# Sheet_1_2022-05-04.net
KiCad netlist of a schematic drawn in Altium Designer
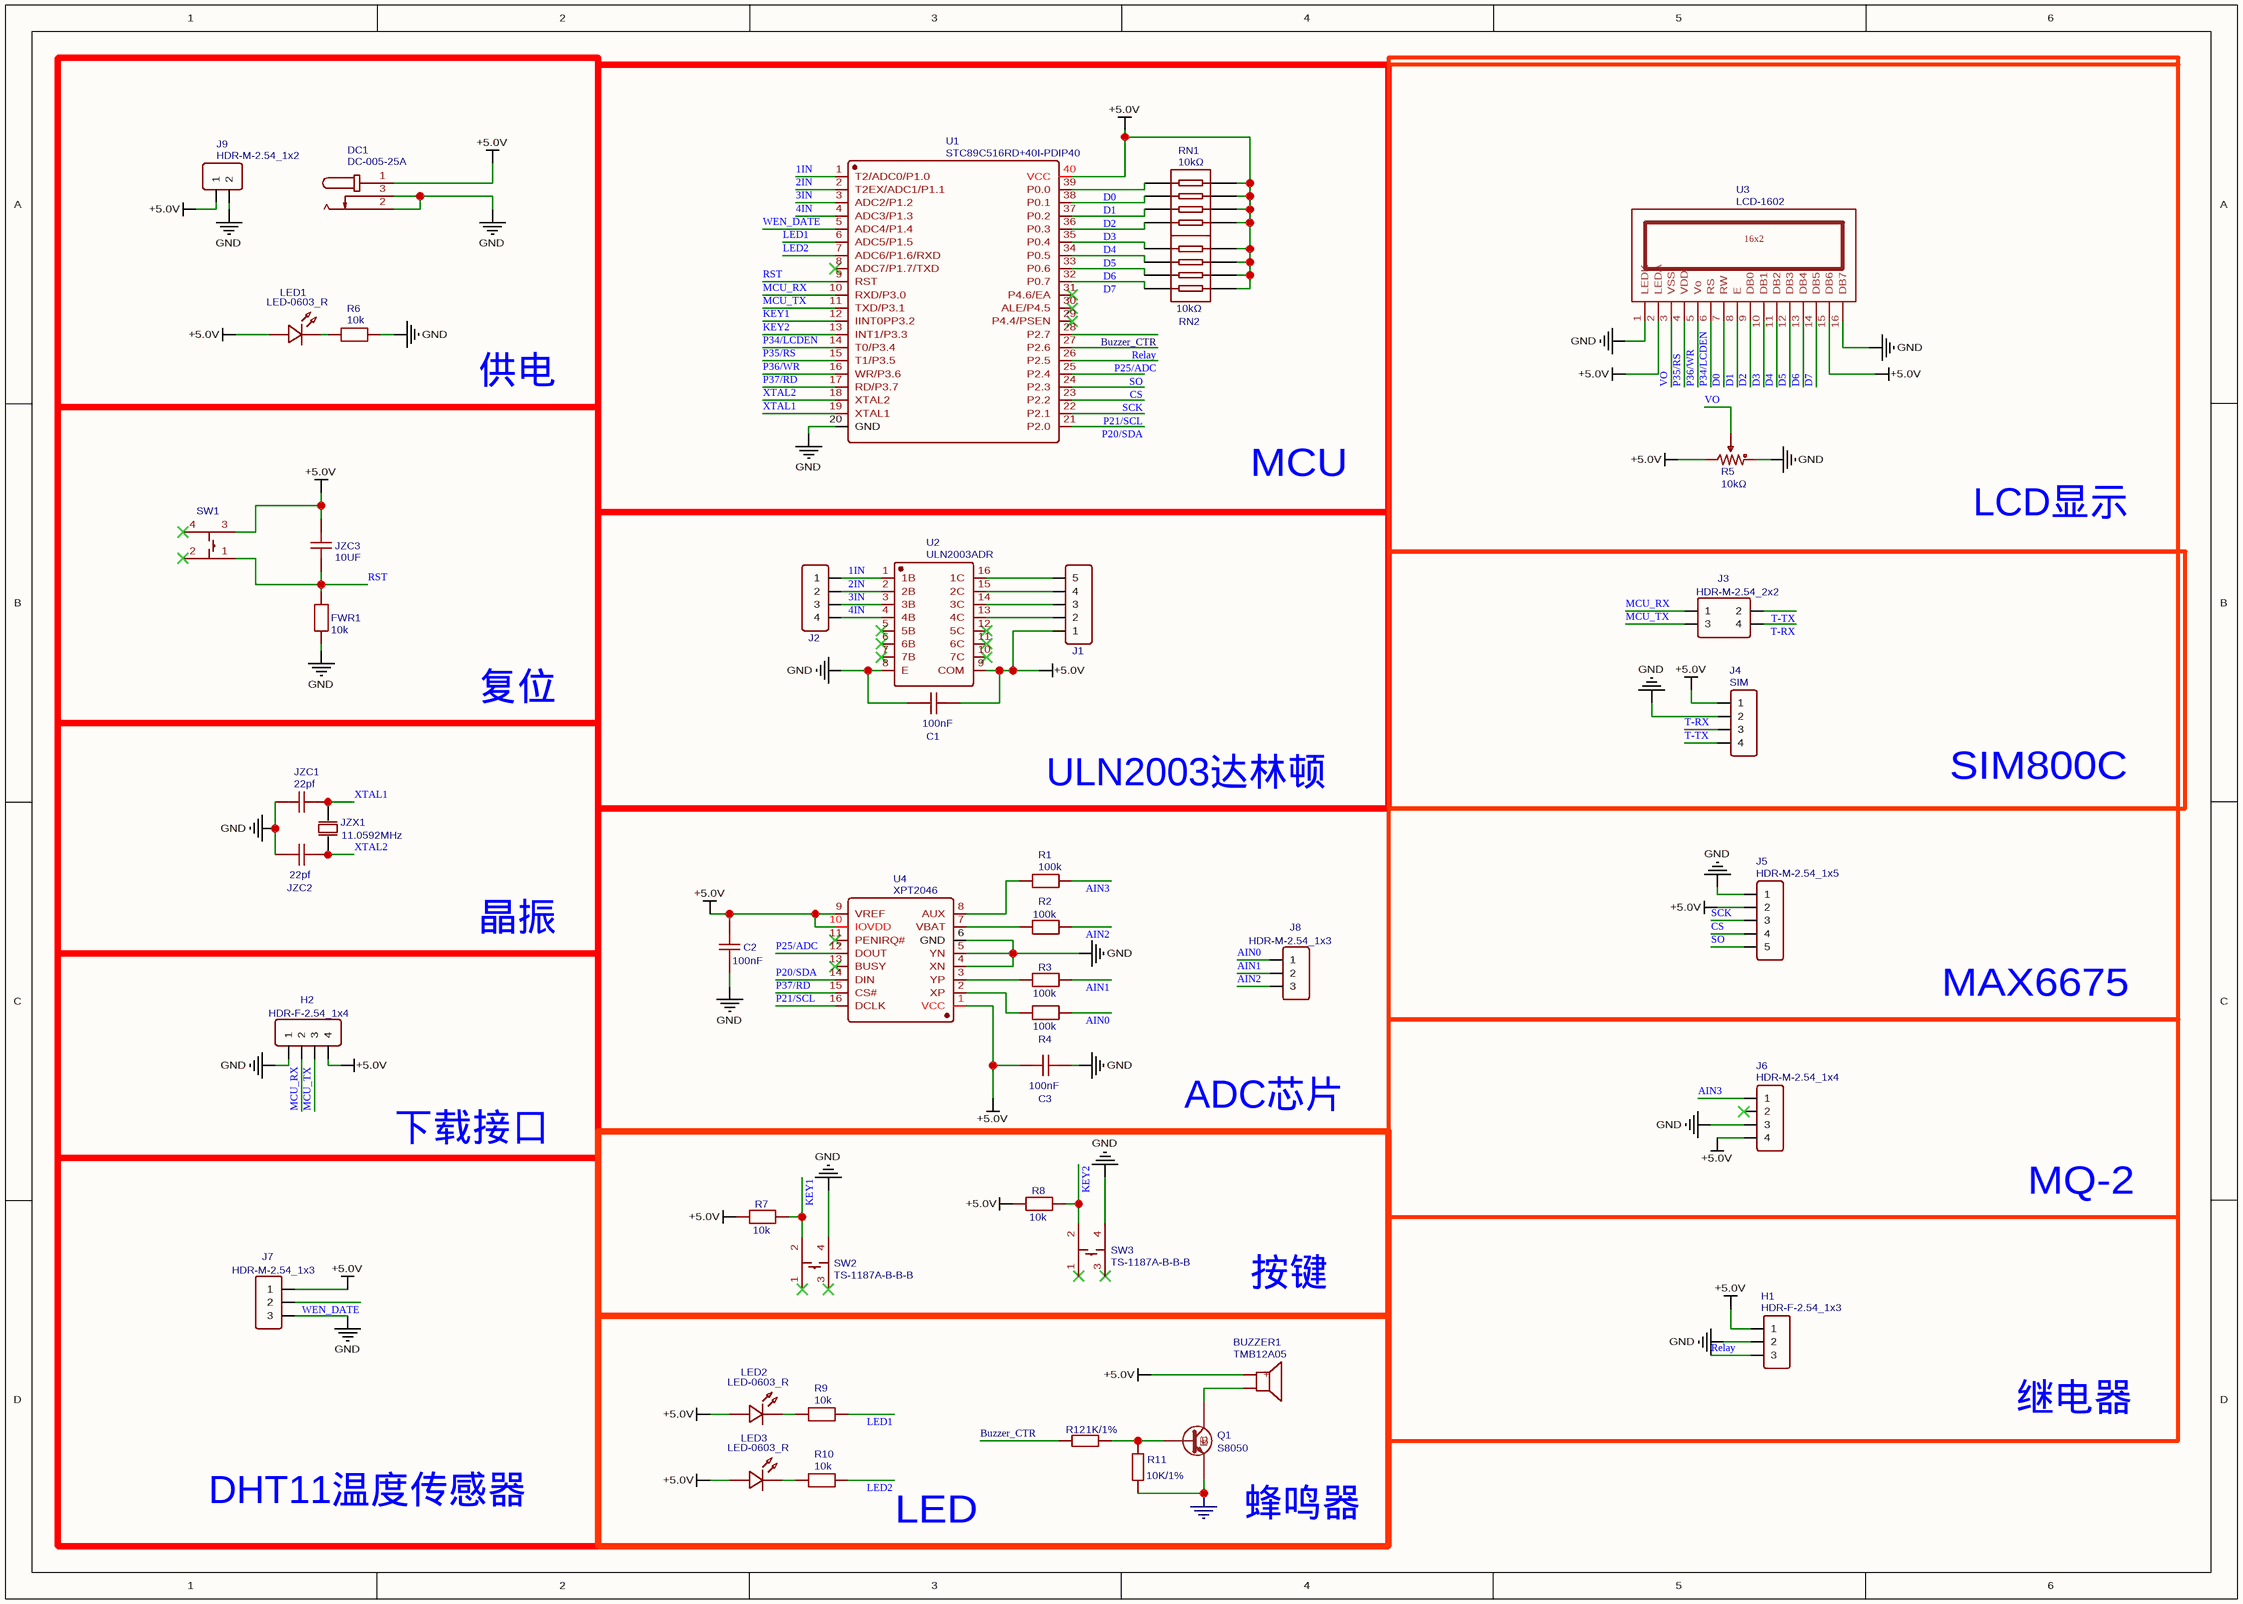
[diagram p0: Sheet_1_2022-05-04.schdoc]

(export (version "E")
  (design (tool "Eeschema 10.0.6"))
  (components
    (comp (ref "BUZZER1")
      (value "TMB12A05")
      (fields (field (name "BOM_SUPPLIER PART") "C96093"))
      (libsource (lib "altium-import") (part "root_0_TMB12A05_"))
    )
    (comp (ref "C1")
      (value "100nF")
      (fields (field (name "CONTRIBUTOR") "LCEDA_Lib"))
      (libsource (lib "altium-import") (part "root_0_100nF_"))
    )
    (comp (ref "C2")
      (value "100nF")
      (fields (field (name "CONTRIBUTOR") "LCEDA_Lib"))
      (libsource (lib "altium-import") (part "root_1_100nF_"))
    )
    (comp (ref "C3")
      (value "100nF")
      (fields (field (name "CONTRIBUTOR") "LCEDA_Lib"))
      (libsource (lib "altium-import") (part "root_0_100nF_"))
    )
    (comp (ref "DC1")
      (value "DC-005-25A")
      (fields (field (name "BOM_SUPPLIER PART") "C136715") (field (name "CONTRIBUTOR") "LCSC"))
      (libsource (lib "altium-import") (part "root_0_DC-005-25A_"))
    )
    (comp (ref "FWR1")
      (value "10k")
      (fields (field (name "CONTRIBUTOR") "LCEDA_Lib"))
      (libsource (lib "altium-import") (part "root_1_10k_"))
    )
    (comp (ref "H1")
      (value "HDR-F-2.54_1x3")
      (fields (field (name "BOM_SUPPLIER PART") "C146690") (field (name "CONTRIBUTOR") "LCEDA_Lib"))
      (libsource (lib "altium-import") (part "root_0_HDR-F-2.54_1x3_"))
    )
    (comp (ref "H2")
      (value "HDR-F-2.54_1x4")
      (fields (field (name "BOM_SUPPLIER PART") "C225501") (field (name "CONTRIBUTOR") "LCEDA_Lib"))
      (libsource (lib "altium-import") (part "root_1_HDR-F-2.54_1x4_"))
    )
    (comp (ref "J1")
      (value "HDR-M-2.54_1x5")
      (fields (field (name "BOM_SUPPLIER PART") "C358687") (field (name "CONTRIBUTOR") "LCEDA_Lib"))
      (libsource (lib "") (part "root_0_HDR-M-2.54_1x5__1"))
    )
    (comp (ref "J2")
      (value "HDR-M-2.54_1x4")
      (fields (field (name "BOM_SUPPLIER PART") "C124378") (field (name "CONTRIBUTOR") "LCEDA_Lib"))
      (libsource (lib "altium-import") (part "root_0_HDR-M-2.54_1x4_"))
    )
    (comp (ref "J3")
      (value "HDR-M-2.54_2x2")
      (fields (field (name "BOM_SUPPLIER PART") "C66690") (field (name "CONTRIBUTOR") "LCEDA_Lib"))
      (libsource (lib "altium-import") (part "root_0_HDR-M-2.54_2x2_"))
    )
    (comp (ref "J4")
      (value "SIM")
      (fields (field (name "BOM_SUPPLIER PART") "C124378") (field (name "CONTRIBUTOR") "LCEDA_Lib"))
      (libsource (lib "altium-import") (part "root_0_SIM_"))
    )
    (comp (ref "J5")
      (value "HDR-M-2.54_1x5")
      (fields (field (name "BOM_SUPPLIER PART") "C358687") (field (name "CONTRIBUTOR") "LCEDA_Lib"))
      (libsource (lib "altium-import") (part "root_0_HDR-M-2.54_1x5_"))
    )
    (comp (ref "J6")
      (value "HDR-M-2.54_1x4")
      (fields (field (name "BOM_SUPPLIER PART") "C124378") (field (name "CONTRIBUTOR") "LCEDA_Lib"))
      (libsource (lib "") (part "root_0_HDR-M-2.54_1x4__1"))
    )
    (comp (ref "J7")
      (value "HDR-M-2.54_1x3")
      (fields (field (name "BOM_SUPPLIER PART") "C180248") (field (name "CONTRIBUTOR") "LCEDA_Lib"))
      (libsource (lib "altium-import") (part "root_0_HDR-M-2.54_1x3_"))
    )
    (comp (ref "J8")
      (value "HDR-M-2.54_1x3")
      (fields (field (name "BOM_SUPPLIER PART") "C180248") (field (name "CONTRIBUTOR") "LCEDA_Lib"))
      (libsource (lib "") (part "root_0_HDR-M-2.54_1x3__1"))
    )
    (comp (ref "J9")
      (value "HDR-M-2.54_1x2")
      (fields (field (name "BOM_SUPPLIER PART") "C124375") (field (name "CONTRIBUTOR") "LCEDA_Lib"))
      (libsource (lib "altium-import") (part "root_1_HDR-M-2.54_1x2_"))
    )
    (comp (ref "JZC1")
      (value "22pf")
      (fields (field (name "CONTRIBUTOR") "LCEDA_Lib"))
      (libsource (lib "altium-import") (part "root_0_22pf_"))
    )
    (comp (ref "JZC2")
      (value "22pf")
      (fields (field (name "CONTRIBUTOR") "LCEDA_Lib"))
      (libsource (lib "altium-import") (part "root_0_22pf_"))
    )
    (comp (ref "JZC3")
      (value "10UF")
      (fields (field (name "CONTRIBUTOR") "LCEDA_Lib"))
      (libsource (lib "altium-import") (part "root_1_10UF_"))
    )
    (comp (ref "JZX1")
      (value "11.0592MHz")
      (fields
        (field (name "BOM_MANUFACTURER PART") "X49SD1431818MSD2SC")
        (field (name "BOM_SUPPLIER PART") "C2206")
      )
      (libsource (lib "altium-import") (part "root_1_11.0592MHz_"))
    )
    (comp (ref "LED1")
      (value "LED-0603_R")
      (fields
        (field (name "BOM_MANUFACTURER PART") "19-217/R6C-AL1M2VY/3T")
        (field (name "BOM_SUPPLIER PART") "C72044")
        (field (name "CONTRIBUTOR") "LCEDA_01")
      )
      (libsource (lib "altium-import") (part "root_0_LED-0603_R_"))
    )
    (comp (ref "LED2")
      (value "LED-0603_R")
      (fields
        (field (name "BOM_MANUFACTURER PART") "19-217/R6C-AL1M2VY/3T")
        (field (name "BOM_SUPPLIER PART") "C72044")
        (field (name "CONTRIBUTOR") "LCEDA_01")
      )
      (libsource (lib "altium-import") (part "root_0_LED-0603_R_"))
    )
    (comp (ref "LED3")
      (value "LED-0603_R")
      (fields
        (field (name "BOM_MANUFACTURER PART") "19-217/R6C-AL1M2VY/3T")
        (field (name "BOM_SUPPLIER PART") "C72044")
        (field (name "CONTRIBUTOR") "LCEDA_01")
      )
      (libsource (lib "altium-import") (part "root_0_LED-0603_R_"))
    )
    (comp (ref "Q1") (value "S8050") (libsource (lib "altium-import") (part "root_0_S8050_")))
    (comp (ref "R1")
      (value "100k")
      (fields (field (name "CONTRIBUTOR") "LCEDA_Lib"))
      (libsource (lib "altium-import") (part "root_0_100k_"))
    )
    (comp (ref "R2")
      (value "100k")
      (fields (field (name "CONTRIBUTOR") "LCEDA_Lib"))
      (libsource (lib "altium-import") (part "root_0_100k_"))
    )
    (comp (ref "R3")
      (value "100k")
      (fields (field (name "CONTRIBUTOR") "LCEDA_Lib"))
      (libsource (lib "altium-import") (part "root_0_100k_"))
    )
    (comp (ref "R4")
      (value "100k")
      (fields (field (name "CONTRIBUTOR") "LCEDA_Lib"))
      (libsource (lib "altium-import") (part "root_0_100k_"))
    )
    (comp (ref "R5")
      (value "10kΩ")
      (fields
        (field (name "BOM_SUPPLIER PART") "C118956")
        (field (name "BOM_MANUFACTURER PART") "3362P-1-103")
        (field (name "CONTRIBUTOR") "LCSC")
      )
      (libsource (lib "") (part "root_0_10kΩ__1"))
    )
    (comp (ref "R6")
      (value "10k")
      (fields (field (name "CONTRIBUTOR") "LCEDA_Lib"))
      (libsource (lib "altium-import") (part "root_2_10k_"))
    )
    (comp (ref "R7")
      (value "10k")
      (fields (field (name "CONTRIBUTOR") "LCEDA_Lib"))
      (libsource (lib "altium-import") (part "root_0_10k_"))
    )
    (comp (ref "R8")
      (value "10k")
      (fields (field (name "CONTRIBUTOR") "LCEDA_Lib"))
      (libsource (lib "altium-import") (part "root_0_10k_"))
    )
    (comp (ref "R9")
      (value "10k")
      (fields (field (name "CONTRIBUTOR") "LCEDA_Lib"))
      (libsource (lib "altium-import") (part "root_2_10k_"))
    )
    (comp (ref "R10")
      (value "10k")
      (fields (field (name "CONTRIBUTOR") "LCEDA_Lib"))
      (libsource (lib "altium-import") (part "root_2_10k_"))
    )
    (comp (ref "R11") (value "10K/1%") (libsource (lib "altium-import") (part "root_1_10K/1%_")))
    (comp (ref "R12") (value "1K/1%") (libsource (lib "altium-import") (part "root_2_1K/1%_")))
    (comp (ref "RN1")
      (value "10kΩ")
      (fields
        (field (name "BOM_MANUFACTURER PART") "4D03WGJ0103T5E")
        (field (name "BOM_SUPPLIER PART") "C29718")
      )
      (libsource (lib "altium-import") (part "root_0_10kΩ_"))
    )
    (comp (ref "RN2")
      (value "10kΩ")
      (fields
        (field (name "BOM_MANUFACTURER PART") "4D03WGJ0103T5E")
        (field (name "BOM_SUPPLIER PART") "C29718")
      )
      (libsource (lib "altium-import") (part "root_0_10kΩ_"))
    )
    (comp (ref "SW1")
      (value "TS-1187A-B-B-B")
      (fields (field (name "BOM_SUPPLIER PART") "C528026") (field (name "CONTRIBUTOR") "LCSC"))
      (libsource (lib "altium-import") (part "root_2_TS-1187A-B-B-B_"))
    )
    (comp (ref "SW2")
      (value "TS-1187A-B-B-B")
      (fields (field (name "BOM_SUPPLIER PART") "C528026") (field (name "CONTRIBUTOR") "LCSC"))
      (libsource (lib "altium-import") (part "root_1_TS-1187A-B-B-B_"))
    )
    (comp (ref "SW3")
      (value "TS-1187A-B-B-B")
      (fields (field (name "BOM_SUPPLIER PART") "C528026") (field (name "CONTRIBUTOR") "LCSC"))
      (libsource (lib "altium-import") (part "root_1_TS-1187A-B-B-B_"))
    )
    (comp (ref "U1")
      (value "STC89C516RD+40I-PDIP40")
      (fields (field (name "BOM_SUPPLIER PART") "C52225"))
      (libsource (lib "altium-import") (part "root_0_STC89C516RD+40I-PDIP40_"))
    )
    (comp (ref "U2")
      (value "ULN2003ADR")
      (fields (field (name "BOM_SUPPLIER PART") "C7512"))
      (libsource (lib "altium-import") (part "root_0_ULN2003ADR_"))
    )
    (comp (ref "U3")
      (value "LCD-1602")
      (fields (field (name "CONTRIBUTOR") "andrewivkh"))
      (libsource (lib "altium-import") (part "root_0_LCD-1602_"))
    )
    (comp (ref "U4")
      (value "XPT2046")
      (fields (field (name "BOM_SUPPLIER PART") "C19076"))
      (libsource (lib "altium-import") (part "root_2_XPT2046_"))
    )
  )
  (nets
    (net (code "1") (name "+5.0V") (class "Default")
      (node (ref "BUZZER1") (pin "1") (pinfunction "+_1") (pintype "passive"))
      (node (ref "C1") (pin "2") (pinfunction "2_2") (pintype "passive"))
      (node (ref "C2") (pin "2") (pinfunction "2_2") (pintype "passive"))
      (node (ref "C3") (pin "1") (pinfunction "1_1") (pintype "passive"))
      (node (ref "DC1") (pin "1") (pinfunction "1_1") (pintype "passive"))
      (node (ref "H1") (pin "1") (pinfunction "1_1") (pintype "passive"))
      (node (ref "H2") (pin "4") (pinfunction "4_4") (pintype "passive"))
      (node (ref "J1") (pin "1") (pinfunction "1_1") (pintype "passive"))
      (node (ref "J4") (pin "1") (pinfunction "1_1") (pintype "passive"))
      (node (ref "J5") (pin "2") (pinfunction "2_2") (pintype "passive"))
      (node (ref "J6") (pin "4") (pinfunction "4_4") (pintype "passive"))
      (node (ref "J7") (pin "1") (pinfunction "1_1") (pintype "passive"))
      (node (ref "J9") (pin "1") (pinfunction "1_1") (pintype "passive"))
      (node (ref "JZC3") (pin "2") (pinfunction "2_2") (pintype "passive"))
      (node (ref "LED1") (pin "1") (pinfunction "1_1") (pintype "passive"))
      (node (ref "LED2") (pin "1") (pinfunction "1_1") (pintype "passive"))
      (node (ref "LED3") (pin "1") (pinfunction "1_1") (pintype "passive"))
      (node (ref "R5") (pin "3") (pinfunction "3_3") (pintype "passive"))
      (node (ref "R7") (pin "1") (pinfunction "1_1") (pintype "passive"))
      (node (ref "R8") (pin "1") (pinfunction "1_1") (pintype "passive"))
      (node (ref "RN1") (pin "5") (pinfunction "5_5") (pintype "passive"))
      (node (ref "RN1") (pin "6") (pinfunction "6_6") (pintype "passive"))
      (node (ref "RN1") (pin "7") (pinfunction "7_7") (pintype "passive"))
      (node (ref "RN1") (pin "8") (pinfunction "8_8") (pintype "passive"))
      (node (ref "RN2") (pin "5") (pinfunction "5_5") (pintype "passive"))
      (node (ref "RN2") (pin "6") (pinfunction "6_6") (pintype "passive"))
      (node (ref "RN2") (pin "7") (pinfunction "7_7") (pintype "passive"))
      (node (ref "RN2") (pin "8") (pinfunction "8_8") (pintype "passive"))
      (node (ref "SW1") (pin "3") (pinfunction "C_3") (pintype "passive"))
      (node (ref "U1") (pin "40") (pinfunction "VCC_40") (pintype "passive"))
      (node (ref "U2") (pin "9") (pinfunction "COM_9") (pintype "passive"))
      (node (ref "U3") (pin "15") (pinfunction "DB6_15") (pintype "passive"))
      (node (ref "U3") (pin "2") (pinfunction "LEDA_2") (pintype "passive"))
      (node (ref "U4") (pin "1") (pinfunction "VCC_1") (pintype "passive"))
      (node (ref "U4") (pin "10") (pinfunction "IOVDD_10") (pintype "passive"))
      (node (ref "U4") (pin "9") (pinfunction "VREF_9") (pintype "passive"))
    )
    (net (code "2") (name "/1IN") (class "Default")
      (node (ref "J2") (pin "1") (pinfunction "1_1") (pintype "passive"))
      (node (ref "U1") (pin "1") (pinfunction "T2/ADC0/P1.0_1") (pintype "passive"))
      (node (ref "U2") (pin "1") (pinfunction "1B_1") (pintype "passive"))
    )
    (net (code "3") (name "/2IN") (class "Default")
      (node (ref "J2") (pin "2") (pinfunction "2_2") (pintype "passive"))
      (node (ref "U1") (pin "2") (pinfunction "T2EX/ADC1/P1.1_2") (pintype "passive"))
      (node (ref "U2") (pin "2") (pinfunction "2B_2") (pintype "passive"))
    )
    (net (code "4") (name "/3IN") (class "Default")
      (node (ref "J2") (pin "3") (pinfunction "3_3") (pintype "passive"))
      (node (ref "U1") (pin "3") (pinfunction "ADC2/P1.2_3") (pintype "passive"))
      (node (ref "U2") (pin "3") (pinfunction "3B_3") (pintype "passive"))
    )
    (net (code "5") (name "/4IN") (class "Default")
      (node (ref "J2") (pin "4") (pinfunction "4_4") (pintype "passive"))
      (node (ref "U1") (pin "4") (pinfunction "ADC3/P1.3_4") (pintype "passive"))
      (node (ref "U2") (pin "4") (pinfunction "4B_4") (pintype "passive"))
    )
    (net (code "6") (name "/AIN0") (class "Default")
      (node (ref "J8") (pin "1") (pinfunction "1_1") (pintype "passive"))
      (node (ref "R4") (pin "2") (pinfunction "2_2") (pintype "passive"))
    )
    (net (code "7") (name "/AIN1") (class "Default")
      (node (ref "J8") (pin "2") (pinfunction "2_2") (pintype "passive"))
      (node (ref "R3") (pin "2") (pinfunction "2_2") (pintype "passive"))
    )
    (net (code "8") (name "/AIN2") (class "Default")
      (node (ref "J8") (pin "3") (pinfunction "3_3") (pintype "passive"))
      (node (ref "R2") (pin "2") (pinfunction "2_2") (pintype "passive"))
    )
    (net (code "9") (name "/AIN3") (class "Default")
      (node (ref "J6") (pin "1") (pinfunction "1_1") (pintype "passive"))
      (node (ref "R1") (pin "2") (pinfunction "2_2") (pintype "passive"))
    )
    (net (code "10") (name "/Buzzer_CTR") (class "Default")
      (node (ref "R12") (pin "2") (pinfunction "2_2") (pintype "passive"))
      (node (ref "U1") (pin "28") (pinfunction "P2.7_28") (pintype "passive"))
    )
    (net (code "11") (name "/CS") (class "Default")
      (node (ref "J5") (pin "4") (pinfunction "4_4") (pintype "passive"))
      (node (ref "U1") (pin "24") (pinfunction "P2.3_24") (pintype "passive"))
    )
    (net (code "12") (name "/D0") (class "Default")
      (node (ref "RN1") (pin "1") (pinfunction "1_1") (pintype "passive"))
      (node (ref "U1") (pin "39") (pinfunction "P0.0_39") (pintype "passive"))
      (node (ref "U3") (pin "7") (pinfunction "RW_7") (pintype "passive"))
    )
    (net (code "13") (name "/D1") (class "Default")
      (node (ref "RN1") (pin "2") (pinfunction "2_2") (pintype "passive"))
      (node (ref "U1") (pin "38") (pinfunction "P0.1_38") (pintype "passive"))
      (node (ref "U3") (pin "8") (pinfunction "E_8") (pintype "passive"))
    )
    (net (code "14") (name "/D2") (class "Default")
      (node (ref "RN1") (pin "3") (pinfunction "3_3") (pintype "passive"))
      (node (ref "U1") (pin "37") (pinfunction "P0.2_37") (pintype "passive"))
      (node (ref "U3") (pin "9") (pinfunction "DB0_9") (pintype "passive"))
    )
    (net (code "15") (name "/D3") (class "Default")
      (node (ref "RN1") (pin "4") (pinfunction "4_4") (pintype "passive"))
      (node (ref "U1") (pin "36") (pinfunction "P0.3_36") (pintype "passive"))
      (node (ref "U3") (pin "10") (pinfunction "DB1_10") (pintype "passive"))
    )
    (net (code "16") (name "/D4") (class "Default")
      (node (ref "RN2") (pin "1") (pinfunction "1_1") (pintype "passive"))
      (node (ref "U1") (pin "35") (pinfunction "P0.4_35") (pintype "passive"))
      (node (ref "U3") (pin "11") (pinfunction "DB2_11") (pintype "passive"))
    )
    (net (code "17") (name "/D5") (class "Default")
      (node (ref "RN2") (pin "2") (pinfunction "2_2") (pintype "passive"))
      (node (ref "U1") (pin "34") (pinfunction "P0.5_34") (pintype "passive"))
      (node (ref "U3") (pin "12") (pinfunction "DB3_12") (pintype "passive"))
    )
    (net (code "18") (name "/D6") (class "Default")
      (node (ref "RN2") (pin "3") (pinfunction "3_3") (pintype "passive"))
      (node (ref "U1") (pin "33") (pinfunction "P0.6_33") (pintype "passive"))
      (node (ref "U3") (pin "13") (pinfunction "DB4_13") (pintype "passive"))
    )
    (net (code "19") (name "/D7") (class "Default")
      (node (ref "RN2") (pin "4") (pinfunction "4_4") (pintype "passive"))
      (node (ref "U1") (pin "32") (pinfunction "P0.7_32") (pintype "passive"))
      (node (ref "U3") (pin "14") (pinfunction "DB5_14") (pintype "passive"))
    )
    (net (code "20") (name "/KEY1") (class "Default")
      (node (ref "R7") (pin "2") (pinfunction "2_2") (pintype "passive"))
      (node (ref "SW2") (pin "2") (pinfunction "B_2") (pintype "passive"))
      (node (ref "U1") (pin "12") (pinfunction "IINT0PP3.2_12") (pintype "passive"))
    )
    (net (code "21") (name "/KEY2") (class "Default")
      (node (ref "R8") (pin "2") (pinfunction "2_2") (pintype "passive"))
      (node (ref "SW3") (pin "2") (pinfunction "B_2") (pintype "passive"))
      (node (ref "U1") (pin "13") (pinfunction "INT1/P3.3_13") (pintype "passive"))
    )
    (net (code "22") (name "/LED1") (class "Default")
      (node (ref "R9") (pin "1") (pinfunction "1_1") (pintype "passive"))
      (node (ref "U1") (pin "6") (pinfunction "ADC5/P1.5_6") (pintype "passive"))
    )
    (net (code "23") (name "/LED2") (class "Default")
      (node (ref "R10") (pin "1") (pinfunction "1_1") (pintype "passive"))
      (node (ref "U1") (pin "7") (pinfunction "ADC6/P1.6/RXD_7") (pintype "passive"))
    )
    (net (code "24") (name "/MCU_RX") (class "Default")
      (node (ref "H2") (pin "2") (pinfunction "2_2") (pintype "passive"))
      (node (ref "J3") (pin "1") (pinfunction "1_1") (pintype "passive"))
      (node (ref "U1") (pin "10") (pinfunction "RXD/P3.0_10") (pintype "passive"))
    )
    (net (code "25") (name "/MCU_TX") (class "Default")
      (node (ref "H2") (pin "3") (pinfunction "3_3") (pintype "passive"))
      (node (ref "J3") (pin "3") (pinfunction "3_3") (pintype "passive"))
      (node (ref "U1") (pin "11") (pinfunction "TXD/P3.1_11") (pintype "passive"))
    )
    (net (code "26") (name "/P20{slash}SDA") (class "Default")
      (node (ref "U1") (pin "21") (pinfunction "P2.0_21") (pintype "passive"))
      (node (ref "U4") (pin "14") (pinfunction "DIN_14") (pintype "passive"))
    )
    (net (code "27") (name "/P21{slash}SCL") (class "Default")
      (node (ref "U1") (pin "22") (pinfunction "P2.1_22") (pintype "passive"))
      (node (ref "U4") (pin "16") (pinfunction "DCLK_16") (pintype "passive"))
    )
    (net (code "28") (name "/P25{slash}ADC") (class "Default")
      (node (ref "U1") (pin "26") (pinfunction "P2.5_26") (pintype "passive"))
      (node (ref "U4") (pin "12") (pinfunction "DOUT_12") (pintype "passive"))
    )
    (net (code "29") (name "/P34{slash}LCDEN") (class "Default")
      (node (ref "U1") (pin "14") (pinfunction "T0/P3.4_14") (pintype "passive"))
      (node (ref "U3") (pin "6") (pinfunction "RS_6") (pintype "passive"))
    )
    (net (code "30") (name "/P35{slash}RS") (class "Default")
      (node (ref "U1") (pin "15") (pinfunction "T1/P3.5_15") (pintype "passive"))
      (node (ref "U3") (pin "4") (pinfunction "VDD_4") (pintype "passive"))
    )
    (net (code "31") (name "/P36{slash}WR") (class "Default")
      (node (ref "U1") (pin "16") (pinfunction "WR/P3.6_16") (pintype "passive"))
      (node (ref "U3") (pin "5") (pinfunction "Vo_5") (pintype "passive"))
    )
    (net (code "32") (name "/P37{slash}RD") (class "Default")
      (node (ref "U1") (pin "17") (pinfunction "RD/P3.7_17") (pintype "passive"))
      (node (ref "U4") (pin "15") (pinfunction "CS#_15") (pintype "passive"))
    )
    (net (code "33") (name "/RST") (class "Default")
      (node (ref "FWR1") (pin "2") (pinfunction "2_2") (pintype "passive"))
      (node (ref "JZC3") (pin "1") (pinfunction "1_1") (pintype "passive"))
      (node (ref "SW1") (pin "1") (pinfunction "A_1") (pintype "passive"))
      (node (ref "U1") (pin "9") (pinfunction "RST_9") (pintype "passive"))
    )
    (net (code "34") (name "/Relay") (class "Default")
      (node (ref "H1") (pin "3") (pinfunction "3_3") (pintype "passive"))
      (node (ref "U1") (pin "27") (pinfunction "P2.6_27") (pintype "passive"))
    )
    (net (code "35") (name "/SCK") (class "Default")
      (node (ref "J5") (pin "3") (pinfunction "3_3") (pintype "passive"))
      (node (ref "U1") (pin "23") (pinfunction "P2.2_23") (pintype "passive"))
    )
    (net (code "36") (name "/SO") (class "Default")
      (node (ref "J5") (pin "5") (pinfunction "5_5") (pintype "passive"))
      (node (ref "U1") (pin "25") (pinfunction "P2.4_25") (pintype "passive"))
    )
    (net (code "37") (name "/T-RX") (class "Default")
      (node (ref "J3") (pin "4") (pinfunction "4_4") (pintype "passive"))
      (node (ref "J4") (pin "3") (pinfunction "3_3") (pintype "passive"))
    )
    (net (code "38") (name "/T-TX") (class "Default")
      (node (ref "J3") (pin "2") (pinfunction "2_2") (pintype "passive"))
      (node (ref "J4") (pin "4") (pinfunction "4_4") (pintype "passive"))
    )
    (net (code "39") (name "/VO") (class "Default")
      (node (ref "R5") (pin "2") (pinfunction "2_2") (pintype "passive"))
      (node (ref "U3") (pin "3") (pinfunction "VSS_3") (pintype "passive"))
    )
    (net (code "40") (name "/WEN_DATE") (class "Default")
      (node (ref "J7") (pin "2") (pinfunction "2_2") (pintype "passive"))
      (node (ref "U1") (pin "5") (pinfunction "ADC4/P1.4_5") (pintype "passive"))
    )
    (net (code "41") (name "/XTAL1") (class "Default")
      (node (ref "JZC1") (pin "2") (pinfunction "2_2") (pintype "passive"))
      (node (ref "JZX1") (pin "1") (pinfunction "OSC1_1") (pintype "passive"))
      (node (ref "U1") (pin "19") (pinfunction "XTAL1_19") (pintype "passive"))
    )
    (net (code "42") (name "/XTAL2") (class "Default")
      (node (ref "JZC2") (pin "2") (pinfunction "2_2") (pintype "passive"))
      (node (ref "JZX1") (pin "2") (pinfunction "OSC2_2") (pintype "passive"))
      (node (ref "U1") (pin "18") (pinfunction "XTAL2_18") (pintype "passive"))
    )
    (net (code "43") (name "GND") (class "Default")
      (node (ref "C1") (pin "1") (pinfunction "1_1") (pintype "passive"))
      (node (ref "C2") (pin "1") (pinfunction "1_1") (pintype "passive"))
      (node (ref "C3") (pin "2") (pinfunction "2_2") (pintype "passive"))
      (node (ref "DC1") (pin "2") (pinfunction "2_2") (pintype "passive"))
      (node (ref "DC1") (pin "3") (pinfunction "3_3") (pintype "passive"))
      (node (ref "FWR1") (pin "1") (pinfunction "1_1") (pintype "passive"))
      (node (ref "H1") (pin "2") (pinfunction "2_2") (pintype "passive"))
      (node (ref "H2") (pin "1") (pinfunction "1_1") (pintype "passive"))
      (node (ref "J4") (pin "2") (pinfunction "2_2") (pintype "passive"))
      (node (ref "J5") (pin "1") (pinfunction "1_1") (pintype "passive"))
      (node (ref "J6") (pin "3") (pinfunction "3_3") (pintype "passive"))
      (node (ref "J7") (pin "3") (pinfunction "3_3") (pintype "passive"))
      (node (ref "J9") (pin "2") (pinfunction "2_2") (pintype "passive"))
      (node (ref "JZC1") (pin "1") (pinfunction "1_1") (pintype "passive"))
      (node (ref "JZC2") (pin "1") (pinfunction "1_1") (pintype "passive"))
      (node (ref "Q1") (pin "2") (pinfunction "E_2") (pintype "passive"))
      (node (ref "R11") (pin "1") (pinfunction "1_1") (pintype "passive"))
      (node (ref "R5") (pin "1") (pinfunction "1_1") (pintype "passive"))
      (node (ref "R6") (pin "1") (pinfunction "1_1") (pintype "passive"))
      (node (ref "SW2") (pin "4") (pinfunction "D_4") (pintype "passive"))
      (node (ref "SW3") (pin "4") (pinfunction "D_4") (pintype "passive"))
      (node (ref "U1") (pin "20") (pinfunction "GND_20") (pintype "passive"))
      (node (ref "U2") (pin "8") (pinfunction "E_8") (pintype "passive"))
      (node (ref "U3") (pin "1") (pinfunction "LEDK_1") (pintype "passive"))
      (node (ref "U3") (pin "16") (pinfunction "DB7_16") (pintype "passive"))
      (node (ref "U4") (pin "4") (pinfunction "XN_4") (pintype "passive"))
      (node (ref "U4") (pin "5") (pinfunction "YN_5") (pintype "passive"))
      (node (ref "U4") (pin "6") (pinfunction "GND_6") (pintype "passive"))
    )
    (net (code "44") (name "Net-(LED1-Pad2)") (class "Default")
      (node (ref "LED1") (pin "2") (pinfunction "2_2") (pintype "passive"))
      (node (ref "R6") (pin "2") (pinfunction "2_2") (pintype "passive"))
    )
    (net (code "45") (name "Net-(LED2-Pad2)") (class "Default")
      (node (ref "LED2") (pin "2") (pinfunction "2_2") (pintype "passive"))
      (node (ref "R9") (pin "2") (pinfunction "2_2") (pintype "passive"))
    )
    (net (code "46") (name "Net-(LED3-Pad2)") (class "Default")
      (node (ref "LED3") (pin "2") (pinfunction "2_2") (pintype "passive"))
      (node (ref "R10") (pin "2") (pinfunction "2_2") (pintype "passive"))
    )
    (net (code "47") (name "Net-(Q1-B)") (class "Default")
      (node (ref "Q1") (pin "1") (pinfunction "B_1") (pintype "passive"))
      (node (ref "R11") (pin "2") (pinfunction "2_2") (pintype "passive"))
      (node (ref "R12") (pin "1") (pinfunction "1_1") (pintype "passive"))
    )
    (net (code "48") (name "Net-(Q1-C)") (class "Default")
      (node (ref "BUZZER1") (pin "2") (pinfunction "2_2") (pintype "passive"))
      (node (ref "Q1") (pin "3") (pinfunction "C_3") (pintype "passive"))
    )
    (net (code "49") (name "Net-(U2-1C)") (class "Default")
      (node (ref "J1") (pin "5") (pinfunction "5_5") (pintype "passive"))
      (node (ref "U2") (pin "16") (pinfunction "1C_16") (pintype "passive"))
    )
    (net (code "50") (name "Net-(U2-2C)") (class "Default")
      (node (ref "J1") (pin "4") (pinfunction "4_4") (pintype "passive"))
      (node (ref "U2") (pin "15") (pinfunction "2C_15") (pintype "passive"))
    )
    (net (code "51") (name "Net-(U2-3C)") (class "Default")
      (node (ref "J1") (pin "3") (pinfunction "3_3") (pintype "passive"))
      (node (ref "U2") (pin "14") (pinfunction "3C_14") (pintype "passive"))
    )
    (net (code "52") (name "Net-(U2-4C)") (class "Default")
      (node (ref "J1") (pin "2") (pinfunction "2_2") (pintype "passive"))
      (node (ref "U2") (pin "13") (pinfunction "4C_13") (pintype "passive"))
    )
    (net (code "53") (name "Net-(U4-AUX)") (class "Default")
      (node (ref "R1") (pin "1") (pinfunction "1_1") (pintype "passive"))
      (node (ref "U4") (pin "8") (pinfunction "AUX_8") (pintype "passive"))
    )
    (net (code "54") (name "Net-(U4-VBAT)") (class "Default")
      (node (ref "R2") (pin "1") (pinfunction "1_1") (pintype "passive"))
      (node (ref "U4") (pin "7") (pinfunction "VBAT_7") (pintype "passive"))
    )
    (net (code "55") (name "Net-(U4-XP)") (class "Default")
      (node (ref "R4") (pin "1") (pinfunction "1_1") (pintype "passive"))
      (node (ref "U4") (pin "2") (pinfunction "XP_2") (pintype "passive"))
    )
    (net (code "56") (name "Net-(U4-YP)") (class "Default")
      (node (ref "R3") (pin "1") (pinfunction "1_1") (pintype "passive"))
      (node (ref "U4") (pin "3") (pinfunction "YP_3") (pintype "passive"))
    )
    (net (code "57") (name "unconnected-(J6-Pad2)") (class "Default")
      (node (ref "J6") (pin "2") (pinfunction "2_2") (pintype "passive+no_connect"))
    )
    (net (code "58") (name "unconnected-(SW1-B-Pad2)") (class "Default")
      (node (ref "SW1") (pin "2") (pinfunction "B_2") (pintype "passive+no_connect"))
    )
    (net (code "59") (name "unconnected-(SW1-D-Pad4)") (class "Default")
      (node (ref "SW1") (pin "4") (pinfunction "D_4") (pintype "passive+no_connect"))
    )
    (net (code "60") (name "unconnected-(SW2-A-Pad1)") (class "Default")
      (node (ref "SW2") (pin "1") (pinfunction "A_1") (pintype "passive+no_connect"))
    )
    (net (code "61") (name "unconnected-(SW2-C-Pad3)") (class "Default")
      (node (ref "SW2") (pin "3") (pinfunction "C_3") (pintype "passive+no_connect"))
    )
    (net (code "62") (name "unconnected-(SW3-A-Pad1)") (class "Default")
      (node (ref "SW3") (pin "1") (pinfunction "A_1") (pintype "passive+no_connect"))
    )
    (net (code "63") (name "unconnected-(SW3-C-Pad3)") (class "Default")
      (node (ref "SW3") (pin "3") (pinfunction "C_3") (pintype "passive+no_connect"))
    )
    (net (code "64") (name "unconnected-(U1-ADC7{slash}P1.7{slash}TXD-Pad8)") (class "Default")
      (node (ref "U1") (pin "8") (pinfunction "ADC7/P1.7/TXD_8") (pintype "passive+no_connect"))
    )
    (net (code "65") (name "unconnected-(U1-ALE{slash}P4.5-Pad30)") (class "Default")
      (node (ref "U1") (pin "30") (pinfunction "ALE/P4.5_30") (pintype "passive+no_connect"))
    )
    (net (code "66") (name "unconnected-(U1-P4.4{slash}PSEN-Pad29)") (class "Default")
      (node (ref "U1") (pin "29") (pinfunction "P4.4/PSEN_29") (pintype "passive+no_connect"))
    )
    (net (code "67") (name "unconnected-(U1-P4.6{slash}EA-Pad31)") (class "Default")
      (node (ref "U1") (pin "31") (pinfunction "P4.6/EA_31") (pintype "passive+no_connect"))
    )
    (net (code "68") (name "unconnected-(U2-5B-Pad5)") (class "Default")
      (node (ref "U2") (pin "5") (pinfunction "5B_5") (pintype "passive+no_connect"))
    )
    (net (code "69") (name "unconnected-(U2-5C-Pad12)") (class "Default")
      (node (ref "U2") (pin "12") (pinfunction "5C_12") (pintype "passive+no_connect"))
    )
    (net (code "70") (name "unconnected-(U2-6B-Pad6)") (class "Default")
      (node (ref "U2") (pin "6") (pinfunction "6B_6") (pintype "passive+no_connect"))
    )
    (net (code "71") (name "unconnected-(U2-6C-Pad11)") (class "Default")
      (node (ref "U2") (pin "11") (pinfunction "6C_11") (pintype "passive+no_connect"))
    )
    (net (code "72") (name "unconnected-(U2-7B-Pad7)") (class "Default")
      (node (ref "U2") (pin "7") (pinfunction "7B_7") (pintype "passive+no_connect"))
    )
    (net (code "73") (name "unconnected-(U2-7C-Pad10)") (class "Default")
      (node (ref "U2") (pin "10") (pinfunction "7C_10") (pintype "passive+no_connect"))
    )
    (net (code "74") (name "unconnected-(U4-BUSY-Pad13)") (class "Default")
      (node (ref "U4") (pin "13") (pinfunction "BUSY_13") (pintype "passive+no_connect"))
    )
    (net (code "75") (name "unconnected-(U4-PENIRQ#-Pad11)") (class "Default")
      (node (ref "U4") (pin "11") (pinfunction "PENIRQ#_11") (pintype "passive+no_connect"))
    )
  )
)
